# rip_head_2018.net
KiCad netlist of a schematic drawn in EAGLE
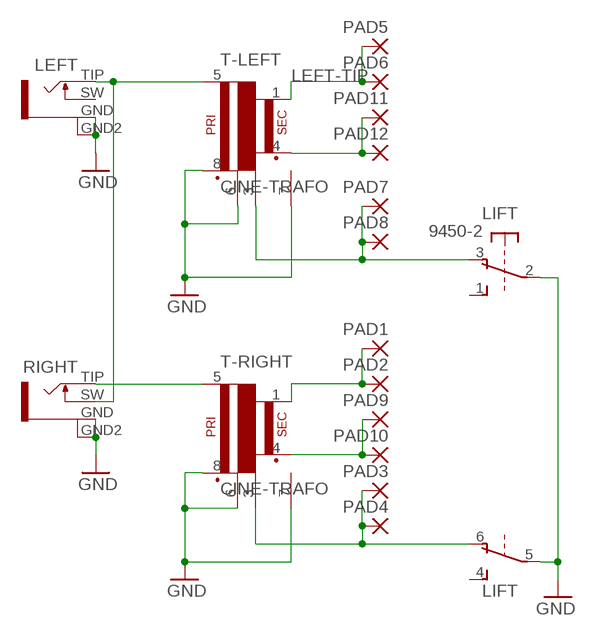
[diagram p0: schematic, sheet 1]

(export (version "E")
  (design (tool "Eeschema 10.0.6"))
  (components
    (comp (ref "LEFT")
      (value "SHAPES_PONY_ERTHENVAR-JACK")
      (footprint "eagle-import:SHAPES_PONY_3.5MMJACK")
      (libsource (lib "eagle-import") (part "SHAPES_PONY_ERTHENVAR-JACK"))
    )
    (comp (ref "LIFT")
      (value "9450-2")
      (footprint "eagle-import:9450-2")
      (libsource (lib "eagle-import") (part "9450-2"))
    )
    (comp (ref "PAD1")
      (value "SMD2")
      (footprint "eagle-import:SMD1,27-2,54")
      (libsource (lib "eagle-import") (part "SMD2"))
    )
    (comp (ref "PAD2")
      (value "SMD2")
      (footprint "eagle-import:SMD1,27-2,54")
      (libsource (lib "eagle-import") (part "SMD2"))
    )
    (comp (ref "PAD3")
      (value "SMD2")
      (footprint "eagle-import:SMD1,27-2,54")
      (libsource (lib "eagle-import") (part "SMD2"))
    )
    (comp (ref "PAD4")
      (value "SMD2")
      (footprint "eagle-import:SMD1,27-2,54")
      (libsource (lib "eagle-import") (part "SMD2"))
    )
    (comp (ref "PAD5")
      (value "SMD2")
      (footprint "eagle-import:SMD1,27-2,54")
      (libsource (lib "eagle-import") (part "SMD2"))
    )
    (comp (ref "PAD6")
      (value "SMD2")
      (footprint "eagle-import:SMD1,27-2,54")
      (libsource (lib "eagle-import") (part "SMD2"))
    )
    (comp (ref "PAD7")
      (value "SMD2")
      (footprint "eagle-import:SMD1,27-2,54")
      (libsource (lib "eagle-import") (part "SMD2"))
    )
    (comp (ref "PAD8")
      (value "SMD2")
      (footprint "eagle-import:SMD1,27-2,54")
      (libsource (lib "eagle-import") (part "SMD2"))
    )
    (comp (ref "PAD9")
      (value "SMD2")
      (footprint "eagle-import:SMD1,27-2,54")
      (libsource (lib "eagle-import") (part "SMD2"))
    )
    (comp (ref "PAD10")
      (value "SMD2")
      (footprint "eagle-import:SMD1,27-2,54")
      (libsource (lib "eagle-import") (part "SMD2"))
    )
    (comp (ref "PAD11")
      (value "SMD2")
      (footprint "eagle-import:SMD1,27-2,54")
      (libsource (lib "eagle-import") (part "SMD2"))
    )
    (comp (ref "PAD12")
      (value "SMD2")
      (footprint "eagle-import:SMD1,27-2,54")
      (libsource (lib "eagle-import") (part "SMD2"))
    )
    (comp (ref "RIGHT")
      (value "SHAPES_PONY_ERTHENVAR-JACK")
      (footprint "eagle-import:SHAPES_PONY_3.5MMJACK")
      (libsource (lib "eagle-import") (part "SHAPES_PONY_ERTHENVAR-JACK"))
    )
    (comp (ref "T-LEFT")
      (value "CINE-TRAFO")
      (footprint "eagle-import:CIRC-TRAFO")
      (libsource (lib "eagle-import") (part "CINE-TRAFO"))
    )
    (comp (ref "T-RIGHT")
      (value "CINE-TRAFO")
      (footprint "eagle-import:CIRC-TRAFO")
      (libsource (lib "eagle-import") (part "CINE-TRAFO"))
    )
  )
  (nets
    (net (code "1") (name "/LEFT-TIP") (class "Default")
      (node (ref "PAD5") (pin "1") (pinfunction "P_1") (pintype "passive"))
      (node (ref "PAD6") (pin "1") (pinfunction "P_1") (pintype "passive"))
      (node (ref "T-LEFT") (pin "1") (pinfunction "S1_1") (pintype "passive"))
    )
    (net (code "2") (name "GND") (class "Default")
      (node (ref "LEFT") (pin "GND") (pinfunction "1_GND") (pintype "passive"))
      (node (ref "LEFT") (pin "GND2") (pinfunction "4_GND2") (pintype "passive"))
      (node (ref "LIFT") (pin "2") (pinfunction "P_2") (pintype "passive"))
      (node (ref "LIFT") (pin "5") (pinfunction "P_5") (pintype "passive"))
      (node (ref "RIGHT") (pin "GND") (pinfunction "1_GND") (pintype "passive"))
      (node (ref "RIGHT") (pin "GND2") (pinfunction "4_GND2") (pintype "passive"))
      (node (ref "T-LEFT") (pin "6") (pinfunction "C1_6") (pintype "passive"))
      (node (ref "T-LEFT") (pin "7") (pinfunction "CASE_7") (pintype "passive"))
      (node (ref "T-LEFT") (pin "8") (pinfunction "P2_8") (pintype "passive"))
      (node (ref "T-RIGHT") (pin "6") (pinfunction "C1_6") (pintype "passive"))
      (node (ref "T-RIGHT") (pin "7") (pinfunction "CASE_7") (pintype "passive"))
      (node (ref "T-RIGHT") (pin "8") (pinfunction "P2_8") (pintype "passive"))
    )
    (net (code "3") (name "Net-(LEFT-2)") (class "Default")
      (node (ref "LEFT") (pin "TIP") (pinfunction "2_TIP") (pintype "passive"))
      (node (ref "RIGHT") (pin "SW") (pinfunction "3_SW") (pintype "passive"))
      (node (ref "T-LEFT") (pin "5") (pinfunction "P1_5") (pintype "passive"))
    )
    (net (code "4") (name "Net-(LIFTA-O)") (class "Default")
      (node (ref "LIFT") (pin "3") (pinfunction "O_3") (pintype "passive"))
      (node (ref "PAD7") (pin "1") (pinfunction "P_1") (pintype "passive"))
      (node (ref "PAD8") (pin "1") (pinfunction "P_1") (pintype "passive"))
      (node (ref "T-LEFT") (pin "3") (pinfunction "C2_3") (pintype "passive"))
    )
    (net (code "5") (name "Net-(LIFTB-O)") (class "Default")
      (node (ref "LIFT") (pin "6") (pinfunction "O_6") (pintype "passive"))
      (node (ref "PAD3") (pin "1") (pinfunction "P_1") (pintype "passive"))
      (node (ref "PAD4") (pin "1") (pinfunction "P_1") (pintype "passive"))
      (node (ref "T-RIGHT") (pin "3") (pinfunction "C2_3") (pintype "passive"))
    )
    (net (code "6") (name "Net-(PAD1-P)") (class "Default")
      (node (ref "PAD1") (pin "1") (pinfunction "P_1") (pintype "passive"))
      (node (ref "PAD2") (pin "1") (pinfunction "P_1") (pintype "passive"))
      (node (ref "T-RIGHT") (pin "1") (pinfunction "S1_1") (pintype "passive"))
    )
    (net (code "7") (name "Net-(PAD10-P)") (class "Default")
      (node (ref "PAD10") (pin "1") (pinfunction "P_1") (pintype "passive"))
      (node (ref "PAD9") (pin "1") (pinfunction "P_1") (pintype "passive"))
      (node (ref "T-RIGHT") (pin "4") (pinfunction "S2_4") (pintype "passive"))
    )
    (net (code "8") (name "Net-(PAD11-P)") (class "Default")
      (node (ref "PAD11") (pin "1") (pinfunction "P_1") (pintype "passive"))
      (node (ref "PAD12") (pin "1") (pinfunction "P_1") (pintype "passive"))
      (node (ref "T-LEFT") (pin "4") (pinfunction "S2_4") (pintype "passive"))
    )
    (net (code "9") (name "Net-(RIGHT-2)") (class "Default")
      (node (ref "RIGHT") (pin "TIP") (pinfunction "2_TIP") (pintype "passive"))
      (node (ref "T-RIGHT") (pin "5") (pinfunction "P1_5") (pintype "passive"))
    )
    (net (code "10") (name "unconnected-(LEFT-3-PadSW)") (class "Default")
      (node (ref "LEFT") (pin "SW") (pinfunction "3_SW") (pintype "passive"))
    )
    (net (code "11") (name "unconnected-(LIFTA-S-Pad1)") (class "Default")
      (node (ref "LIFT") (pin "1") (pinfunction "S_1") (pintype "passive"))
    )
    (net (code "12") (name "unconnected-(LIFTB-S-Pad4)") (class "Default")
      (node (ref "LIFT") (pin "4") (pinfunction "S_4") (pintype "passive"))
    )
  )
)
